# Power_main_DCDC.net
KiCad netlist of a schematic drawn in Altium Designer
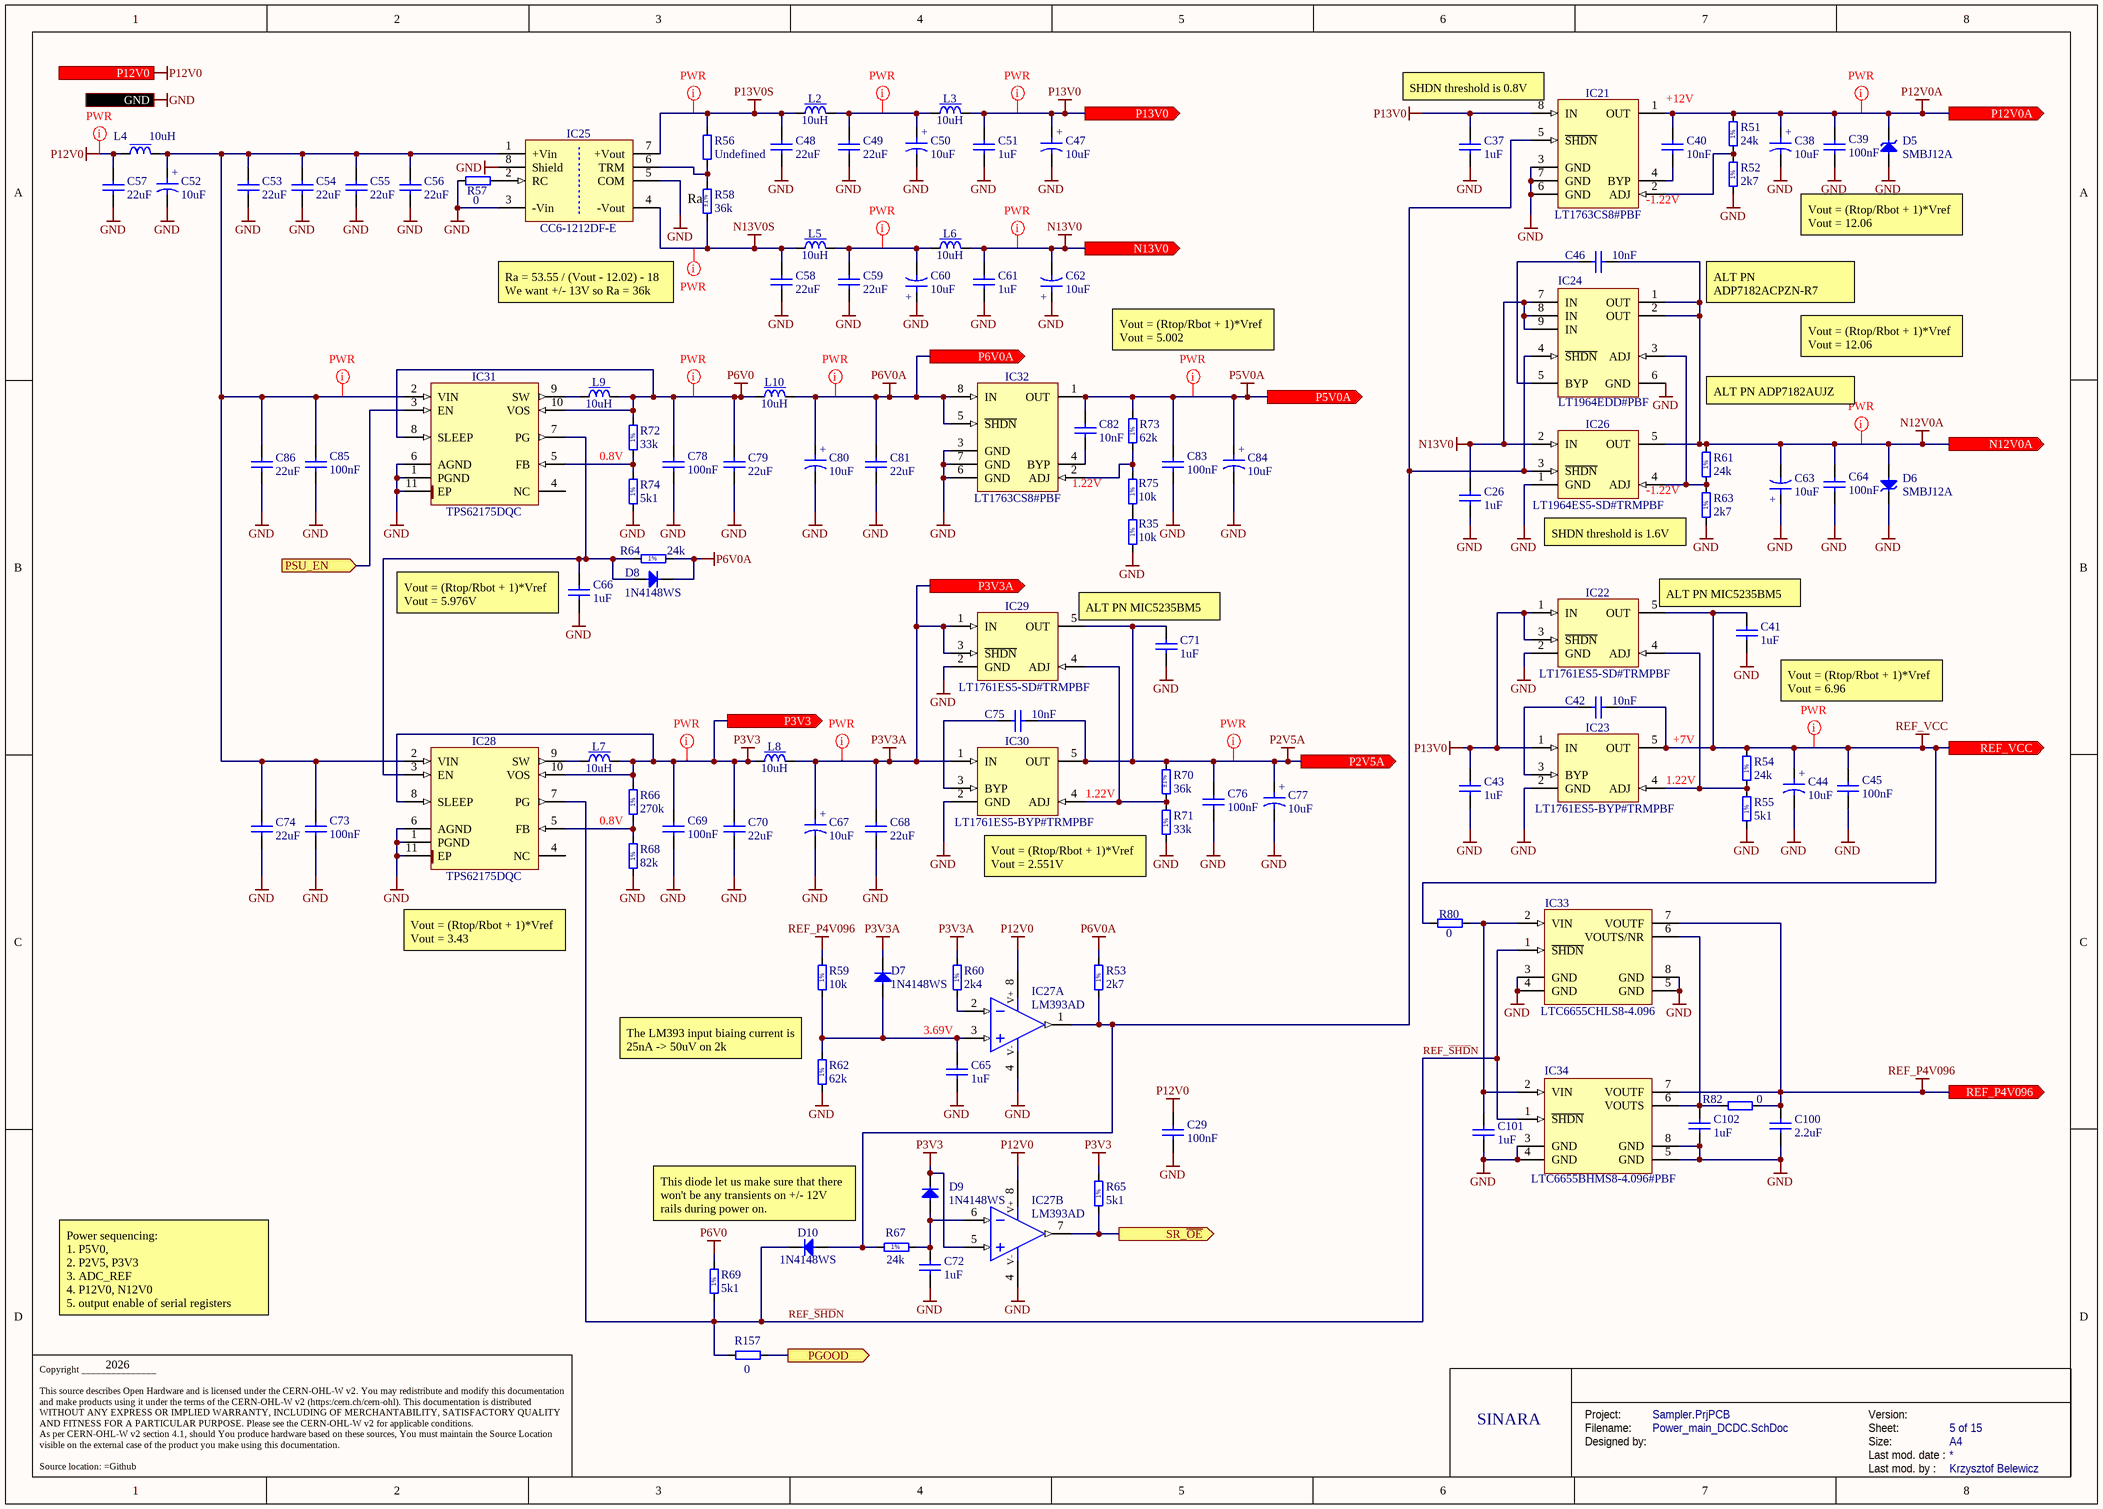
[diagram p0: Power_main_DCDC.SchDoc]

(export (version "E")
  (design (tool "Eeschema 10.0.6"))
  (components
    (comp (ref "C26")
      (value "1uF")
      (footprint "CAPC1608X87N")
      (description "Non-polarised capacitor")
      (fields
        (field (name "PART NUMBER") "CC0603_1UF_25V_10%_X7R")
        (field (name "VOLTAGE") "25V")
        (field (name "AUTHOR") "CERN DEM JLC")
      )
      (libsource (lib "Capacitors") (part "Capacitor - non polarized"))
    )
    (comp (ref "C29")
      (value "100nF")
      (footprint "CAPC1005X55N")
      (description "Non-polarised capacitor")
      (fields
        (field (name "PART NUMBER") "CC0402_100NF_50V_10%_X7R")
        (field (name "VOLTAGE") "50V")
        (field (name "AUTHOR") "CERN DEM MR")
      )
      (libsource (lib "Capacitors") (part "Capacitor - non polarized"))
    )
    (comp (ref "C37")
      (value "1uF")
      (footprint "CAPC1608X87N")
      (description "Non-polarised capacitor")
      (fields
        (field (name "PART NUMBER") "CC0603_1UF_25V_10%_X7R")
        (field (name "VOLTAGE") "25V")
        (field (name "AUTHOR") "CERN DEM JLC")
      )
      (libsource (lib "Capacitors") (part "Capacitor - non polarized"))
    )
    (comp (ref "C38")
      (value "10uF")
      (footprint "CAPMP3216X180N")
      (description "Polarised capacitor")
      (fields
        (field (name "PART NUMBER") "CTE3216-18_10UF_16V_20%_AVX_TCJ")
        (field (name "VOLTAGE") "16V")
        (field (name "AUTHOR") "CERN DEM JLC")
      )
      (libsource (lib "Capacitors") (part "Capacitor - polarized"))
    )
    (comp (ref "C39")
      (value "100nF")
      (footprint "CAPC1005X55N")
      (description "Non-polarised capacitor")
      (fields
        (field (name "PART NUMBER") "CC0402_100NF_50V_10%_X7R")
        (field (name "VOLTAGE") "50V")
        (field (name "AUTHOR") "CERN DEM MR")
      )
      (libsource (lib "Capacitors") (part "Capacitor - non polarized"))
    )
    (comp (ref "C40")
      (value "10nF")
      (footprint "CAPC1005X55N")
      (description "Non-polarised capacitor")
      (fields
        (field (name "PART NUMBER") "CC0402_10NF_50V_5%_X7R")
        (field (name "VOLTAGE") "50V")
        (field (name "AUTHOR") "CERN DEM BC")
      )
      (libsource (lib "Capacitors") (part "Capacitor - non polarized"))
    )
    (comp (ref "C41")
      (value "1uF")
      (footprint "CAPC1608X87N")
      (description "Non-polarised capacitor")
      (fields
        (field (name "PART NUMBER") "CC0603_1UF_25V_10%_X7R")
        (field (name "VOLTAGE") "25V")
        (field (name "AUTHOR") "CERN DEM JLC")
      )
      (libsource (lib "Capacitors") (part "Capacitor - non polarized"))
    )
    (comp (ref "C42")
      (value "10nF")
      (footprint "CAPC1005X55N")
      (description "Non-polarised capacitor")
      (fields
        (field (name "PART NUMBER") "CC0402_10NF_50V_5%_X7R")
        (field (name "VOLTAGE") "50V")
        (field (name "AUTHOR") "CERN DEM BC")
      )
      (libsource (lib "Capacitors") (part "Capacitor - non polarized"))
    )
    (comp (ref "C43")
      (value "1uF")
      (footprint "CAPC1608X87N")
      (description "Non-polarised capacitor")
      (fields
        (field (name "PART NUMBER") "CC0603_1UF_25V_10%_X7R")
        (field (name "VOLTAGE") "25V")
        (field (name "AUTHOR") "CERN DEM JLC")
      )
      (libsource (lib "Capacitors") (part "Capacitor - non polarized"))
    )
    (comp (ref "C44")
      (value "10uF")
      (footprint "CAPMP3216X180N")
      (description "Polarised capacitor")
      (fields
        (field (name "PART NUMBER") "CTE3216-18_10UF_16V_20%_AVX_TCJ")
        (field (name "VOLTAGE") "16V")
        (field (name "AUTHOR") "CERN DEM JLC")
      )
      (libsource (lib "Capacitors") (part "Capacitor - polarized"))
    )
    (comp (ref "C45")
      (value "100nF")
      (footprint "CAPC1005X55N")
      (description "Non-polarised capacitor")
      (fields
        (field (name "PART NUMBER") "CC0402_100NF_50V_10%_X7R")
        (field (name "VOLTAGE") "50V")
        (field (name "AUTHOR") "CERN DEM MR")
      )
      (libsource (lib "Capacitors") (part "Capacitor - non polarized"))
    )
    (comp (ref "C46")
      (value "10nF")
      (footprint "CAPC1005X55N")
      (description "Non-polarised capacitor")
      (fields
        (field (name "PART NUMBER") "CC0402_10NF_50V_5%_X7R")
        (field (name "VOLTAGE") "50V")
        (field (name "AUTHOR") "CERN DEM BC")
      )
      (libsource (lib "Capacitors") (part "Capacitor - non polarized"))
    )
    (comp (ref "C47")
      (value "10uF")
      (footprint "CAPMP3216X180N")
      (description "Polarised capacitor")
      (fields
        (field (name "PART NUMBER") "CTE3216-18_10UF_16V_20%_AVX_TCJ")
        (field (name "VOLTAGE") "16V")
        (field (name "AUTHOR") "CERN DEM JLC")
      )
      (libsource (lib "Capacitors") (part "Capacitor - polarized"))
    )
    (comp (ref "C48")
      (value "22uF")
      (footprint "CAPC2012X135N")
      (description "Non-polarised capacitor")
      (fields
        (field (name "PART NUMBER") "CC0805_22UF_16V_10%_X5R")
        (field (name "VOLTAGE") "16V")
        (field (name "AUTHOR") "CERN DEM JLC")
      )
      (libsource (lib "Capacitors") (part "Capacitor - non polarized"))
    )
    (comp (ref "C49")
      (value "22uF")
      (footprint "CAPC2012X135N")
      (description "Non-polarised capacitor")
      (fields
        (field (name "PART NUMBER") "CC0805_22UF_16V_10%_X5R")
        (field (name "VOLTAGE") "16V")
        (field (name "AUTHOR") "CERN DEM JLC")
      )
      (libsource (lib "Capacitors") (part "Capacitor - non polarized"))
    )
    (comp (ref "C50")
      (value "10uF")
      (footprint "CAPMP3216X180N")
      (description "Polarised capacitor")
      (fields
        (field (name "PART NUMBER") "CTE3216-18_10UF_16V_20%_AVX_TCJ")
        (field (name "VOLTAGE") "16V")
        (field (name "AUTHOR") "CERN DEM JLC")
      )
      (libsource (lib "Capacitors") (part "Capacitor - polarized"))
    )
    (comp (ref "C51")
      (value "1uF")
      (footprint "CAPC1608X87N")
      (description "Non-polarised capacitor")
      (fields
        (field (name "PART NUMBER") "CC0603_1UF_25V_10%_X7R")
        (field (name "VOLTAGE") "25V")
        (field (name "AUTHOR") "CERN DEM JLC")
      )
      (libsource (lib "Capacitors") (part "Capacitor - non polarized"))
    )
    (comp (ref "C52")
      (value "10uF")
      (footprint "CAPMP3216X180N")
      (description "Polarised capacitor")
      (fields
        (field (name "PART NUMBER") "CTE3216-18_10UF_16V_20%_AVX_TCJ")
        (field (name "VOLTAGE") "16V")
        (field (name "AUTHOR") "CERN DEM JLC")
      )
      (libsource (lib "Capacitors") (part "Capacitor - polarized"))
    )
    (comp (ref "C53")
      (value "22uF")
      (footprint "CAPC2012X135N")
      (description "Non-polarised capacitor")
      (fields
        (field (name "PART NUMBER") "CC0805_22UF_16V_10%_X5R")
        (field (name "VOLTAGE") "16V")
        (field (name "AUTHOR") "CERN DEM JLC")
      )
      (libsource (lib "Capacitors") (part "Capacitor - non polarized"))
    )
    (comp (ref "C54")
      (value "22uF")
      (footprint "CAPC2012X135N")
      (description "Non-polarised capacitor")
      (fields
        (field (name "PART NUMBER") "CC0805_22UF_16V_10%_X5R")
        (field (name "VOLTAGE") "16V")
        (field (name "AUTHOR") "CERN DEM JLC")
      )
      (libsource (lib "Capacitors") (part "Capacitor - non polarized"))
    )
    (comp (ref "C55")
      (value "22uF")
      (footprint "CAPC2012X135N")
      (description "Non-polarised capacitor")
      (fields
        (field (name "PART NUMBER") "CC0805_22UF_16V_10%_X5R")
        (field (name "VOLTAGE") "16V")
        (field (name "AUTHOR") "CERN DEM JLC")
      )
      (libsource (lib "Capacitors") (part "Capacitor - non polarized"))
    )
    (comp (ref "C56")
      (value "22uF")
      (footprint "CAPC2012X135N")
      (description "Non-polarised capacitor")
      (fields
        (field (name "PART NUMBER") "CC0805_22UF_16V_10%_X5R")
        (field (name "VOLTAGE") "16V")
        (field (name "AUTHOR") "CERN DEM JLC")
      )
      (libsource (lib "Capacitors") (part "Capacitor - non polarized"))
    )
    (comp (ref "C57")
      (value "22uF")
      (footprint "CAPC2012X135N")
      (description "Non-polarised capacitor")
      (fields
        (field (name "PART NUMBER") "CC0805_22UF_16V_10%_X5R")
        (field (name "VOLTAGE") "16V")
        (field (name "AUTHOR") "CERN DEM JLC")
      )
      (libsource (lib "Capacitors") (part "Capacitor - non polarized"))
    )
    (comp (ref "C58")
      (value "22uF")
      (footprint "CAPC2012X135N")
      (description "Non-polarised capacitor")
      (fields
        (field (name "PART NUMBER") "CC0805_22UF_16V_10%_X5R")
        (field (name "VOLTAGE") "16V")
        (field (name "AUTHOR") "CERN DEM JLC")
      )
      (libsource (lib "Capacitors") (part "Capacitor - non polarized"))
    )
    (comp (ref "C59")
      (value "22uF")
      (footprint "CAPC2012X135N")
      (description "Non-polarised capacitor")
      (fields
        (field (name "PART NUMBER") "CC0805_22UF_16V_10%_X5R")
        (field (name "VOLTAGE") "16V")
        (field (name "AUTHOR") "CERN DEM JLC")
      )
      (libsource (lib "Capacitors") (part "Capacitor - non polarized"))
    )
    (comp (ref "C60")
      (value "10uF")
      (footprint "CAPMP3216X180N")
      (description "Polarised capacitor")
      (fields
        (field (name "PART NUMBER") "CTE3216-18_10UF_16V_20%_AVX_TCJ")
        (field (name "VOLTAGE") "16V")
        (field (name "AUTHOR") "CERN DEM JLC")
      )
      (libsource (lib "Capacitors") (part "Capacitor - polarized"))
    )
    (comp (ref "C61")
      (value "1uF")
      (footprint "CAPC1608X87N")
      (description "Non-polarised capacitor")
      (fields
        (field (name "PART NUMBER") "CC0603_1UF_25V_10%_X7R")
        (field (name "VOLTAGE") "25V")
        (field (name "AUTHOR") "CERN DEM JLC")
      )
      (libsource (lib "Capacitors") (part "Capacitor - non polarized"))
    )
    (comp (ref "C62")
      (value "10uF")
      (footprint "CAPMP3216X180N")
      (description "Polarised capacitor")
      (fields
        (field (name "PART NUMBER") "CTE3216-18_10UF_16V_20%_AVX_TCJ")
        (field (name "VOLTAGE") "16V")
        (field (name "AUTHOR") "CERN DEM JLC")
      )
      (libsource (lib "Capacitors") (part "Capacitor - polarized"))
    )
    (comp (ref "C63")
      (value "10uF")
      (footprint "CAPMP3216X180N")
      (description "Polarised capacitor")
      (fields
        (field (name "PART NUMBER") "CTE3216-18_10UF_16V_20%_AVX_TCJ")
        (field (name "VOLTAGE") "16V")
        (field (name "AUTHOR") "CERN DEM JLC")
      )
      (libsource (lib "Capacitors") (part "Capacitor - polarized"))
    )
    (comp (ref "C64")
      (value "100nF")
      (footprint "CAPC1005X55N")
      (description "Non-polarised capacitor")
      (fields
        (field (name "PART NUMBER") "CC0402_100NF_50V_10%_X7R")
        (field (name "VOLTAGE") "50V")
        (field (name "AUTHOR") "CERN DEM MR")
      )
      (libsource (lib "Capacitors") (part "Capacitor - non polarized"))
    )
    (comp (ref "C65")
      (value "1uF")
      (footprint "CAPC1608X87N")
      (description "Non-polarised capacitor")
      (fields
        (field (name "PART NUMBER") "CC0603_1UF_25V_10%_X7R")
        (field (name "VOLTAGE") "25V")
        (field (name "AUTHOR") "CERN DEM JLC")
      )
      (libsource (lib "Capacitors") (part "Capacitor - non polarized"))
    )
    (comp (ref "C66")
      (value "1uF")
      (footprint "CAPC1608X87N")
      (description "Non-polarised capacitor")
      (fields
        (field (name "PART NUMBER") "CC0603_1UF_25V_10%_X7R")
        (field (name "VOLTAGE") "25V")
        (field (name "AUTHOR") "CERN DEM JLC")
      )
      (libsource (lib "Capacitors") (part "Capacitor - non polarized"))
    )
    (comp (ref "C67")
      (value "10uF")
      (footprint "CAPMP3216X180N")
      (description "Polarised capacitor")
      (fields
        (field (name "PART NUMBER") "CTE3216-18_10UF_16V_20%_AVX_TCJ")
        (field (name "VOLTAGE") "16V")
        (field (name "AUTHOR") "CERN DEM JLC")
      )
      (libsource (lib "Capacitors") (part "Capacitor - polarized"))
    )
    (comp (ref "C68")
      (value "22uF")
      (footprint "CAPC2012X135N")
      (description "Non-polarised capacitor")
      (fields
        (field (name "PART NUMBER") "CC0805_22UF_16V_10%_X5R")
        (field (name "VOLTAGE") "16V")
        (field (name "AUTHOR") "CERN DEM JLC")
      )
      (libsource (lib "Capacitors") (part "Capacitor - non polarized"))
    )
    (comp (ref "C69")
      (value "100nF")
      (footprint "CAPC1005X55N")
      (description "Non-polarised capacitor")
      (fields
        (field (name "PART NUMBER") "CC0402_100NF_50V_10%_X7R")
        (field (name "VOLTAGE") "50V")
        (field (name "AUTHOR") "CERN DEM MR")
      )
      (libsource (lib "Capacitors") (part "Capacitor - non polarized"))
    )
    (comp (ref "C70")
      (value "22uF")
      (footprint "CAPC2012X135N")
      (description "Non-polarised capacitor")
      (fields
        (field (name "PART NUMBER") "CC0805_22UF_16V_10%_X5R")
        (field (name "VOLTAGE") "16V")
        (field (name "AUTHOR") "CERN DEM JLC")
      )
      (libsource (lib "Capacitors") (part "Capacitor - non polarized"))
    )
    (comp (ref "C71")
      (value "1uF")
      (footprint "CAPC1608X87N")
      (description "Non-polarised capacitor")
      (fields
        (field (name "PART NUMBER") "CC0603_1UF_25V_10%_X7R")
        (field (name "VOLTAGE") "25V")
        (field (name "AUTHOR") "CERN DEM JLC")
      )
      (libsource (lib "Capacitors") (part "Capacitor - non polarized"))
    )
    (comp (ref "C72")
      (value "1uF")
      (footprint "CAPC1608X87N")
      (description "Non-polarised capacitor")
      (fields
        (field (name "PART NUMBER") "CC0603_1UF_25V_10%_X7R")
        (field (name "VOLTAGE") "25V")
        (field (name "AUTHOR") "CERN DEM JLC")
      )
      (libsource (lib "Capacitors") (part "Capacitor - non polarized"))
    )
    (comp (ref "C73")
      (value "100nF")
      (footprint "CAPC1005X55N")
      (description "Non-polarised capacitor")
      (fields
        (field (name "PART NUMBER") "CC0402_100NF_50V_10%_X7R")
        (field (name "VOLTAGE") "50V")
        (field (name "AUTHOR") "CERN DEM MR")
      )
      (libsource (lib "Capacitors") (part "Capacitor - non polarized"))
    )
    (comp (ref "C74")
      (value "22uF")
      (footprint "CAPC2012X135N")
      (description "Non-polarised capacitor")
      (fields
        (field (name "PART NUMBER") "CC0805_22UF_16V_10%_X5R")
        (field (name "VOLTAGE") "16V")
        (field (name "AUTHOR") "CERN DEM JLC")
      )
      (libsource (lib "Capacitors") (part "Capacitor - non polarized"))
    )
    (comp (ref "C75")
      (value "10nF")
      (footprint "CAPC1005X55N")
      (description "Non-polarised capacitor")
      (fields
        (field (name "PART NUMBER") "CC0402_10NF_50V_5%_X7R")
        (field (name "VOLTAGE") "50V")
        (field (name "AUTHOR") "CERN DEM BC")
      )
      (libsource (lib "Capacitors") (part "Capacitor - non polarized"))
    )
    (comp (ref "C76")
      (value "100nF")
      (footprint "CAPC1005X55N")
      (description "Non-polarised capacitor")
      (fields
        (field (name "PART NUMBER") "CC0402_100NF_50V_10%_X7R")
        (field (name "VOLTAGE") "50V")
        (field (name "AUTHOR") "CERN DEM MR")
      )
      (libsource (lib "Capacitors") (part "Capacitor - non polarized"))
    )
    (comp (ref "C77")
      (value "10uF")
      (footprint "CAPMP3216X180N")
      (description "Polarised capacitor")
      (fields
        (field (name "PART NUMBER") "CTE3216-18_10UF_16V_20%_AVX_TCJ")
        (field (name "VOLTAGE") "16V")
        (field (name "AUTHOR") "CERN DEM JLC")
      )
      (libsource (lib "Capacitors") (part "Capacitor - polarized"))
    )
    (comp (ref "C78")
      (value "100nF")
      (footprint "CAPC1005X55N")
      (description "Non-polarised capacitor")
      (fields
        (field (name "PART NUMBER") "CC0402_100NF_50V_10%_X7R")
        (field (name "VOLTAGE") "50V")
        (field (name "AUTHOR") "CERN DEM MR")
      )
      (libsource (lib "Capacitors") (part "Capacitor - non polarized"))
    )
    (comp (ref "C79")
      (value "22uF")
      (footprint "CAPC2012X135N")
      (description "Non-polarised capacitor")
      (fields
        (field (name "PART NUMBER") "CC0805_22UF_16V_10%_X5R")
        (field (name "VOLTAGE") "16V")
        (field (name "AUTHOR") "CERN DEM JLC")
      )
      (libsource (lib "Capacitors") (part "Capacitor - non polarized"))
    )
    (comp (ref "C80")
      (value "10uF")
      (footprint "CAPMP3216X180N")
      (description "Polarised capacitor")
      (fields
        (field (name "PART NUMBER") "CTE3216-18_10UF_16V_20%_AVX_TCJ")
        (field (name "VOLTAGE") "16V")
        (field (name "AUTHOR") "CERN DEM JLC")
      )
      (libsource (lib "Capacitors") (part "Capacitor - polarized"))
    )
    (comp (ref "C81")
      (value "22uF")
      (footprint "CAPC2012X135N")
      (description "Non-polarised capacitor")
      (fields
        (field (name "PART NUMBER") "CC0805_22UF_16V_10%_X5R")
        (field (name "VOLTAGE") "16V")
        (field (name "AUTHOR") "CERN DEM JLC")
      )
      (libsource (lib "Capacitors") (part "Capacitor - non polarized"))
    )
    (comp (ref "C82")
      (value "10nF")
      (footprint "CAPC1005X55N")
      (description "Non-polarised capacitor")
      (fields
        (field (name "PART NUMBER") "CC0402_10NF_50V_5%_X7R")
        (field (name "VOLTAGE") "50V")
        (field (name "AUTHOR") "CERN DEM BC")
      )
      (libsource (lib "Capacitors") (part "Capacitor - non polarized"))
    )
    (comp (ref "C83")
      (value "100nF")
      (footprint "CAPC1005X55N")
      (description "Non-polarised capacitor")
      (fields
        (field (name "PART NUMBER") "CC0402_100NF_50V_10%_X7R")
        (field (name "VOLTAGE") "50V")
        (field (name "AUTHOR") "CERN DEM MR")
      )
      (libsource (lib "Capacitors") (part "Capacitor - non polarized"))
    )
    (comp (ref "C84")
      (value "10uF")
      (footprint "CAPMP3216X180N")
      (description "Polarised capacitor")
      (fields
        (field (name "PART NUMBER") "CTE3216-18_10UF_16V_20%_AVX_TCJ")
        (field (name "VOLTAGE") "16V")
        (field (name "AUTHOR") "CERN DEM JLC")
      )
      (libsource (lib "Capacitors") (part "Capacitor - polarized"))
    )
    (comp (ref "C85")
      (value "100nF")
      (footprint "CAPC1005X55N")
      (description "Non-polarised capacitor")
      (fields
        (field (name "PART NUMBER") "CC0402_100NF_50V_10%_X7R")
        (field (name "VOLTAGE") "50V")
        (field (name "AUTHOR") "CERN DEM MR")
      )
      (libsource (lib "Capacitors") (part "Capacitor - non polarized"))
    )
    (comp (ref "C86")
      (value "22uF")
      (footprint "CAPC2012X135N")
      (description "Non-polarised capacitor")
      (fields
        (field (name "PART NUMBER") "CC0805_22UF_16V_10%_X5R")
        (field (name "VOLTAGE") "16V")
        (field (name "AUTHOR") "CERN DEM JLC")
      )
      (libsource (lib "Capacitors") (part "Capacitor - non polarized"))
    )
    (comp (ref "C100")
      (value "2.2uF")
      (footprint "CAPC1608X87N")
      (description "Non-polarised capacitor")
      (fields
        (field (name "PART NUMBER") "CC0603_2.2UF_16V_10%_X5R")
        (field (name "VOLTAGE") "16V")
        (field (name "AUTHOR") "CERN DEM JLC")
      )
      (libsource (lib "Capacitors") (part "Capacitor - non polarized"))
    )
    (comp (ref "C101")
      (value "1uF")
      (footprint "CAPC1608X87N")
      (description "Non-polarised capacitor")
      (fields
        (field (name "PART NUMBER") "CC0603_1UF_25V_10%_X7R")
        (field (name "VOLTAGE") "25V")
        (field (name "AUTHOR") "CERN DEM JLC")
      )
      (libsource (lib "Capacitors") (part "Capacitor - non polarized"))
    )
    (comp (ref "C102")
      (value "1uF")
      (footprint "CAPC1608X87N")
      (description "Non-polarised capacitor")
      (fields
        (field (name "PART NUMBER") "CC0603_1UF_25V_10%_X7R")
        (field (name "VOLTAGE") "25V")
        (field (name "AUTHOR") "CERN DEM JLC")
      )
      (libsource (lib "Capacitors") (part "Capacitor - non polarized"))
    )
    (comp (ref "D5")
      (value "SMBJ12A")
      (footprint "DIOM5336X265N")
      (description "Zener Diode")
      (fields
        (field (name "VOLTAGE") "12V")
        (field (name "POWER") "600W")
        (field (name "AUTHOR") "CERN DEM JLC")
      )
      (libsource (lib "ICs And Semiconductors") (part "Diode Zener"))
    )
    (comp (ref "D6")
      (value "SMBJ12A")
      (footprint "DIOM5336X265N")
      (description "Zener Diode")
      (fields
        (field (name "VOLTAGE") "12V")
        (field (name "POWER") "600W")
        (field (name "AUTHOR") "CERN DEM JLC")
      )
      (libsource (lib "ICs And Semiconductors") (part "Diode Zener"))
    )
    (comp (ref "D7")
      (value "1N4148WS")
      (footprint "SODFL2512X100N")
      (description "Diode")
      (fields
        (field (name "VOLTAGE") "75V")
        (field (name "POWER") "150mA")
        (field (name "AUTHOR") "CERN DEM JLC")
      )
      (libsource (lib "ICs And Semiconductors") (part "Diode"))
    )
    (comp (ref "D8")
      (value "1N4148WS")
      (footprint "SODFL2512X100N")
      (description "Diode")
      (fields
        (field (name "VOLTAGE") "75V")
        (field (name "POWER") "150mA")
        (field (name "AUTHOR") "CERN DEM JLC")
      )
      (libsource (lib "ICs And Semiconductors") (part "Diode"))
    )
    (comp (ref "D9")
      (value "1N4148WS")
      (footprint "SODFL2512X100N")
      (description "Diode")
      (fields
        (field (name "VOLTAGE") "75V")
        (field (name "POWER") "150mA")
        (field (name "AUTHOR") "CERN DEM JLC")
      )
      (libsource (lib "ICs And Semiconductors") (part "Diode"))
    )
    (comp (ref "D10")
      (value "1N4148WS")
      (footprint "SODFL2512X100N")
      (description "Diode")
      (fields
        (field (name "VOLTAGE") "75V")
        (field (name "POWER") "150mA")
        (field (name "AUTHOR") "CERN DEM JLC")
      )
      (libsource (lib "ICs And Semiconductors") (part "Diode"))
    )
    (comp (ref "IC21")
      (value "LT1763CS8#PBF")
      (footprint "SOIC127P600X175-8N")
      (description "1.22V to 20V 500mA, Low Noise, LDO Adjustable Micropower Regulator")
      (fields (field (name "MANUFACTURER") "LINEAR TECHNOLOGY") (field (name "AUTHOR") "CERN DEM JLC"))
      (libsource (lib "ICs And Semiconductors") (part "LT1763xS8"))
    )
    (comp (ref "IC22")
      (value "LT1761ES5-SD#TRMPBF")
      (footprint "SOT95P280X100-5N")
      (description "100mA, Low Noise, LDO Micropower Adjustable Regulator in SOT-23")
      (fields (field (name "MANUFACTURER") "LINEAR TECHNOLOGY") (field (name "AUTHOR") "CERN DEM JLC"))
      (libsource (lib "ICs And Semiconductors") (part "LT1761-SD"))
    )
    (comp (ref "IC23")
      (value "LT1761ES5-BYP#TRMPBF")
      (footprint "SOT95P280X100-5N")
      (description "100mA, Low Noise, LDO Micropower Adjustable Regulator in SOT-23")
      (fields (field (name "MANUFACTURER") "LINEAR TECHNOLOGY") (field (name "AUTHOR") "CERN DEM MR"))
      (libsource (lib "ICs And Semiconductors") (part "LT1761-BYP"))
    )
    (comp (ref "IC24")
      (value "LT1964EDD#PBF")
      (footprint "LT-DD-8_V")
      (fields (field (name "MANUFACTURER") "Linear Technology"))
      (libsource (lib "Altium Content Vault") (part "LT-LT1964-DD-8"))
    )
    (comp (ref "IC25")
      (value "CC6-1212DF-E")
      (footprint "CC6-1212DF-E")
      (description "CONV DC/DC 6W DUAL 12V +-12V PCB")
      (fields (field (name "MANUFACTURER") "TDK-Lambda Americas Inc.") (field (name "AUTHOR") "GK"))
      (libsource (lib "Regulators_SMPS") (part "DC/DC_CC6-1212DF-E"))
    )
    (comp (ref "IC26")
      (value "LT1964ES5-SD#TRMPBF")
      (footprint "SOT95P280X100-5N")
      (description "200mA, Low Noise, Low Dropout Negative Micropower Regulator")
      (fields (field (name "MANUFACTURER") "LINEAR TECHNOLOGY") (field (name "AUTHOR") "CERN DEM JLC"))
      (libsource (lib "ICs And Semiconductors") (part "LT1964-SD"))
    )
    (comp (ref "IC27")
      (value "LM393AD")
      (footprint "SOIC127P600X175-8N")
      (description "Dual Operational Amplifier")
      (fields (field (name "MANUFACTURER") "TEXAS INSTRUMENTS") (field (name "AUTHOR") "CERN DEM JLC"))
      (libsource (lib "ICs And Semiconductors") (part "Operational Amplifier x2 Type1"))
    )
    (comp (ref "IC28")
      (value "TPS62175DQC")
      (footprint "SON50P200X300X80-11N-R94X250")
      (description "4.75-28VDC to 1-6VDC, 500mA Step-Down Converter With Sleep Mode")
      (fields (field (name "MANUFACTURER") "TEXAS INSTRUMENTS") (field (name "AUTHOR") "CERN DEM JMW"))
      (libsource (lib "ICs And Semiconductors") (part "TPS62175"))
    )
    (comp (ref "IC29")
      (value "LT1761ES5-SD#TRMPBF")
      (footprint "SOT95P280X100-5N")
      (description "100mA, Low Noise, LDO Micropower Adjustable Regulator in SOT-23")
      (fields (field (name "MANUFACTURER") "LINEAR TECHNOLOGY") (field (name "AUTHOR") "CERN DEM JLC"))
      (libsource (lib "ICs And Semiconductors") (part "LT1761-SD"))
    )
    (comp (ref "IC30")
      (value "LT1761ES5-BYP#TRMPBF")
      (footprint "SOT95P280X100-5N")
      (description "100mA, Low Noise, LDO Micropower Adjustable Regulator in SOT-23")
      (fields (field (name "MANUFACTURER") "LINEAR TECHNOLOGY") (field (name "AUTHOR") "CERN DEM MR"))
      (libsource (lib "ICs And Semiconductors") (part "LT1761-BYP"))
    )
    (comp (ref "IC31")
      (value "TPS62175DQC")
      (footprint "SON50P200X300X80-11N-R94X250")
      (description "4.75-28VDC to 1-6VDC, 500mA Step-Down Converter With Sleep Mode")
      (fields (field (name "MANUFACTURER") "TEXAS INSTRUMENTS") (field (name "AUTHOR") "CERN DEM JMW"))
      (libsource (lib "ICs And Semiconductors") (part "TPS62175"))
    )
    (comp (ref "IC32")
      (value "LT1763CS8#PBF")
      (footprint "SOIC127P600X175-8N")
      (description "1.22V to 20V 500mA, Low Noise, LDO Adjustable Micropower Regulator")
      (fields (field (name "MANUFACTURER") "LINEAR TECHNOLOGY") (field (name "AUTHOR") "CERN DEM JLC"))
      (libsource (lib "ICs And Semiconductors") (part "LT1763xS8"))
    )
    (comp (ref "IC33")
      (value "LTC6655CHLS8-4.096")
      (footprint "LCCS127P500X500X145-8N")
      (description "4.096, 1uA Precision Voltage Reference")
      (fields
        (field (name "PART NUMBER") "LTC6655CHLS8-4.096#PBF")
        (field (name "MANUFACTURER") "LINEAR TECHNOLOGY")
        (field (name "AUTHOR") "GK")
      )
      (libsource (lib "ICs_Analog_Interfaces") (part "REF_LTC6655CHLS8-4.096"))
    )
    (comp (ref "IC34")
      (value "LTC6655BHMS8-4.096#PBF")
      (footprint "SOP65P490X110-8N")
      (description "0.25ppm Noise, Low Drift Precision Buffered Voltage Reference")
      (fields (field (name "MANUFACTURER") "LINEAR TECHNOLOGY") (field (name "AUTHOR") "GK"))
      (libsource (lib "LIBRARY_SCH") (part "REF_LTC6655"))
    )
    (comp (ref "L2")
      (value "10uH")
      (footprint "IND_MURATA-PS_8400")
      (description "Inductor With Core")
      (fields
        (field (name "PART NUMBER") "IND_10UH_10%_MURATA-PS_8400")
        (field (name "POWER") "950mA")
        (field (name "AUTHOR") "CERN DEM JLC")
      )
      (libsource (lib "Inductors & Transformers") (part "Inductor With Magnetic core"))
    )
    (comp (ref "L3")
      (value "10uH")
      (footprint "IND_MURATA-PS_8400")
      (description "Inductor With Core")
      (fields
        (field (name "PART NUMBER") "IND_10UH_10%_MURATA-PS_8400")
        (field (name "POWER") "950mA")
        (field (name "AUTHOR") "CERN DEM JLC")
      )
      (libsource (lib "Inductors & Transformers") (part "Inductor With Magnetic core"))
    )
    (comp (ref "L4")
      (value "10uH")
      (footprint "IND_MURATA-PS_8400")
      (description "Inductor With Core")
      (fields
        (field (name "PART NUMBER") "IND_10UH_10%_MURATA-PS_8400")
        (field (name "POWER") "950mA")
        (field (name "AUTHOR") "CERN DEM JLC")
      )
      (libsource (lib "Inductors & Transformers") (part "Inductor With Magnetic core"))
    )
    (comp (ref "L5")
      (value "10uH")
      (footprint "IND_MURATA-PS_8400")
      (description "Inductor With Core")
      (fields
        (field (name "PART NUMBER") "IND_10UH_10%_MURATA-PS_8400")
        (field (name "POWER") "950mA")
        (field (name "AUTHOR") "CERN DEM JLC")
      )
      (libsource (lib "Inductors & Transformers") (part "Inductor With Magnetic core"))
    )
    (comp (ref "L6")
      (value "10uH")
      (footprint "IND_MURATA-PS_8400")
      (description "Inductor With Core")
      (fields
        (field (name "PART NUMBER") "IND_10UH_10%_MURATA-PS_8400")
        (field (name "POWER") "950mA")
        (field (name "AUTHOR") "CERN DEM JLC")
      )
      (libsource (lib "Inductors & Transformers") (part "Inductor With Magnetic core"))
    )
    (comp (ref "L7")
      (value "10uH")
      (footprint "IND_MURATA-PS_8400")
      (description "Inductor With Core")
      (fields
        (field (name "PART NUMBER") "IND_10UH_10%_MURATA-PS_8400")
        (field (name "POWER") "950mA")
        (field (name "AUTHOR") "CERN DEM JLC")
      )
      (libsource (lib "Inductors & Transformers") (part "Inductor With Magnetic core"))
    )
    (comp (ref "L8")
      (value "10uH")
      (footprint "IND_MURATA-PS_8400")
      (description "Inductor With Core")
      (fields
        (field (name "PART NUMBER") "IND_10UH_10%_MURATA-PS_8400")
        (field (name "POWER") "950mA")
        (field (name "AUTHOR") "CERN DEM JLC")
      )
      (libsource (lib "Inductors & Transformers") (part "Inductor With Magnetic core"))
    )
    (comp (ref "L9")
      (value "10uH")
      (footprint "IND_MURATA-PS_8400")
      (description "Inductor With Core")
      (fields
        (field (name "PART NUMBER") "IND_10UH_10%_MURATA-PS_8400")
        (field (name "POWER") "950mA")
        (field (name "AUTHOR") "CERN DEM JLC")
      )
      (libsource (lib "Inductors & Transformers") (part "Inductor With Magnetic core"))
    )
    (comp (ref "L10")
      (value "10uH")
      (footprint "IND_MURATA-PS_8400")
      (description "Inductor With Core")
      (fields
        (field (name "PART NUMBER") "IND_10UH_10%_MURATA-PS_8400")
        (field (name "POWER") "950mA")
        (field (name "AUTHOR") "CERN DEM JLC")
      )
      (libsource (lib "Inductors & Transformers") (part "Inductor With Magnetic core"))
    )
    (comp (ref "R35")
      (value "10k")
      (footprint "RESC1005X40N")
      (description "Resistor - 1%")
      (fields
        (field (name "PART NUMBER") "R0402_10K_1%_0.0625W_100PPM")
        (field (name "POWER") "0.0625W")
        (field (name "AUTHOR") "CERN DEM JLC")
      )
      (libsource (lib "Resistors") (part "Resistor - 1%"))
    )
    (comp (ref "R51")
      (value "24k")
      (footprint "RESC1608X55N")
      (description "Resistor - 1%")
      (fields
        (field (name "PART NUMBER") "R0603_24K_1%_0.1W_100PPM")
        (field (name "POWER") "0.1W")
        (field (name "AUTHOR") "CERN DEM JLC")
      )
      (libsource (lib "Resistors") (part "Resistor - 1%"))
    )
    (comp (ref "R52")
      (value "2k7")
      (footprint "RESC1608X55N")
      (description "Resistor - 1%")
      (fields
        (field (name "PART NUMBER") "R0603_2K7_1%_0.1W_100PPM")
        (field (name "POWER") "0.1W")
        (field (name "AUTHOR") "CERN DEM JLC")
      )
      (libsource (lib "Resistors") (part "Resistor - 1%"))
    )
    (comp (ref "R53")
      (value "2k7")
      (footprint "RESC1608X55N")
      (description "Resistor - 1%")
      (fields
        (field (name "PART NUMBER") "R0603_2K7_1%_0.1W_100PPM")
        (field (name "POWER") "0.1W")
        (field (name "AUTHOR") "CERN DEM JLC")
      )
      (libsource (lib "Resistors") (part "Resistor - 1%"))
    )
    (comp (ref "R54")
      (value "24k")
      (footprint "RESC1608X55N")
      (description "Resistor - 1%")
      (fields
        (field (name "PART NUMBER") "R0603_24K_1%_0.1W_100PPM")
        (field (name "POWER") "0.1W")
        (field (name "AUTHOR") "CERN DEM JLC")
      )
      (libsource (lib "Resistors") (part "Resistor - 1%"))
    )
    (comp (ref "R55")
      (value "5k1")
      (footprint "RESC1005X40N")
      (description "Resistor - 1%")
      (fields
        (field (name "PART NUMBER") "R0402_5K1_1%_0.0625W_100PPM")
        (field (name "POWER") "0.0625W")
        (field (name "AUTHOR") "CERN DEM JLC")
      )
      (libsource (lib "Resistors") (part "Resistor - 1%"))
    )
    (comp (ref "R56")
      (value "Undefined")
      (footprint "RESC1608X55N")
      (description "Resistor")
      (fields (field (name "PART NUMBER") "R0603_NO-VALUE") (field (name "AUTHOR") "CERN DEM JLC"))
      (libsource (lib "Resistors") (part "Resistor"))
    )
    (comp (ref "R57")
      (value "0")
      (footprint "RESC1005X40N")
      (description "Resistor")
      (fields
        (field (name "PART NUMBER") "R0402_0R_JUMPER")
        (field (name "MANUFACTURER") "GENERIC")
        (field (name "AUTHOR") "CERN DEM JLC")
      )
      (libsource (lib "Resistors") (part "Resistor"))
    )
    (comp (ref "R58")
      (value "36k")
      (footprint "RESC1608X55N")
      (description "Resistor - 1%")
      (fields
        (field (name "PART NUMBER") "R0603_36K_1%_0.1W_100PPM")
        (field (name "POWER") "0.1W")
        (field (name "TOLERANCE") "±1%")
        (field (name "AUTHOR") "CERN DEM JLC")
      )
      (libsource (lib "") (part "Resistor - 1%_1"))
    )
    (comp (ref "R59")
      (value "10k")
      (footprint "RESC1005X40N")
      (description "Resistor - 1%")
      (fields
        (field (name "PART NUMBER") "R0402_10K_1%_0.0625W_100PPM")
        (field (name "POWER") "0.0625W")
        (field (name "AUTHOR") "CERN DEM JLC")
      )
      (libsource (lib "Resistors") (part "Resistor - 1%"))
    )
    (comp (ref "R60")
      (value "2k4")
      (footprint "RESC1005X40N")
      (description "Resistor - 1%")
      (fields
        (field (name "PART NUMBER") "R0402_2K4_1%_0.0625W_100PPM")
        (field (name "POWER") "0.0625W")
        (field (name "AUTHOR") "CERN DEM JLC")
      )
      (libsource (lib "Resistors") (part "Resistor - 1%"))
    )
    (comp (ref "R61")
      (value "24k")
      (footprint "RESC1608X55N")
      (description "Resistor - 1%")
      (fields
        (field (name "PART NUMBER") "R0603_24K_1%_0.1W_100PPM")
        (field (name "POWER") "0.1W")
        (field (name "AUTHOR") "CERN DEM JLC")
      )
      (libsource (lib "Resistors") (part "Resistor - 1%"))
    )
    (comp (ref "R62")
      (value "62k")
      (footprint "RESC1005X40N")
      (description "Resistor - 1%")
      (fields
        (field (name "PART NUMBER") "R0402_62K_1%_0.0625W_100PPM")
        (field (name "POWER") "0.0625W")
        (field (name "AUTHOR") "CERN DEM JLC")
      )
      (libsource (lib "Resistors") (part "Resistor - 1%"))
    )
    (comp (ref "R63")
      (value "2k7")
      (footprint "RESC1608X55N")
      (description "Resistor - 1%")
      (fields
        (field (name "PART NUMBER") "R0603_2K7_1%_0.1W_100PPM")
        (field (name "POWER") "0.1W")
        (field (name "AUTHOR") "CERN DEM JLC")
      )
      (libsource (lib "Resistors") (part "Resistor - 1%"))
    )
    (comp (ref "R64")
      (value "24k")
      (footprint "RESC1608X55N")
      (description "Resistor - 1%")
      (fields
        (field (name "PART NUMBER") "R0603_24K_1%_0.1W_100PPM")
        (field (name "POWER") "0.1W")
        (field (name "AUTHOR") "CERN DEM JLC")
      )
      (libsource (lib "Resistors") (part "Resistor - 1%"))
    )
    (comp (ref "R65")
      (value "5k1")
      (footprint "RESC1005X40N")
      (description "Resistor - 1%")
      (fields
        (field (name "PART NUMBER") "R0402_5K1_1%_0.0625W_100PPM")
        (field (name "POWER") "0.0625W")
        (field (name "AUTHOR") "CERN DEM JLC")
      )
      (libsource (lib "Resistors") (part "Resistor - 1%"))
    )
    (comp (ref "R66")
      (value "270k")
      (footprint "RESC1608X55N")
      (description "Resistor - 1%")
      (fields
        (field (name "PART NUMBER") "R0603_270K_1%_0.1W_100PPM")
        (field (name "POWER") "0.1W")
        (field (name "AUTHOR") "CERN DEM JLC")
      )
      (libsource (lib "Resistors") (part "Resistor - 1%"))
    )
    (comp (ref "R67")
      (value "24k")
      (footprint "RESC1608X55N")
      (description "Resistor - 1%")
      (fields
        (field (name "PART NUMBER") "R0603_24K_1%_0.1W_100PPM")
        (field (name "POWER") "0.1W")
        (field (name "AUTHOR") "CERN DEM JLC")
      )
      (libsource (lib "Resistors") (part "Resistor - 1%"))
    )
    (comp (ref "R68")
      (value "82k")
      (footprint "RESC1608X55N")
      (description "Resistor - 1%")
      (fields
        (field (name "PART NUMBER") "R0603_82K_1%_0.1W_100PPM")
        (field (name "POWER") "0.1W")
        (field (name "AUTHOR") "CERN DEM JLC")
      )
      (libsource (lib "Resistors") (part "Resistor - 1%"))
    )
    (comp (ref "R69")
      (value "5k1")
      (footprint "RESC1005X40N")
      (description "Resistor - 1%")
      (fields
        (field (name "PART NUMBER") "R0402_5K1_1%_0.0625W_100PPM")
        (field (name "POWER") "0.0625W")
        (field (name "AUTHOR") "CERN DEM JLC")
      )
      (libsource (lib "Resistors") (part "Resistor - 1%"))
    )
    (comp (ref "R70")
      (value "36k")
      (footprint "RESC1608X55N")
      (description "Resistor - 1%")
      (fields
        (field (name "PART NUMBER") "R0603_36K_1%_0.1W_100PPM")
        (field (name "POWER") "0.1W")
        (field (name "TOLERANCE") "±1%")
        (field (name "AUTHOR") "CERN DEM JLC")
      )
      (libsource (lib "") (part "Resistor - 1%_1"))
    )
    (comp (ref "R71")
      (value "33k")
      (footprint "RESC1005X40N")
      (description "Resistor - 1%")
      (fields
        (field (name "PART NUMBER") "R0402_33K_1%_0.0625W_100PPM")
        (field (name "POWER") "0.0625W")
        (field (name "AUTHOR") "CERN DEM JLC")
      )
      (libsource (lib "Resistors") (part "Resistor - 1%"))
    )
    (comp (ref "R72")
      (value "33k")
      (footprint "RESC1005X40N")
      (description "Resistor - 1%")
      (fields
        (field (name "PART NUMBER") "R0402_33K_1%_0.0625W_100PPM")
        (field (name "POWER") "0.0625W")
        (field (name "AUTHOR") "CERN DEM JLC")
      )
      (libsource (lib "Resistors") (part "Resistor - 1%"))
    )
    (comp (ref "R73")
      (value "62k")
      (footprint "RESC1005X40N")
      (description "Resistor - 1%")
      (fields
        (field (name "PART NUMBER") "R0402_62K_1%_0.0625W_100PPM")
        (field (name "POWER") "0.0625W")
        (field (name "AUTHOR") "CERN DEM JLC")
      )
      (libsource (lib "Resistors") (part "Resistor - 1%"))
    )
    (comp (ref "R74")
      (value "5k1")
      (footprint "RESC1005X40N")
      (description "Resistor - 1%")
      (fields
        (field (name "PART NUMBER") "R0402_5K1_1%_0.0625W_100PPM")
        (field (name "POWER") "0.0625W")
        (field (name "AUTHOR") "CERN DEM JLC")
      )
      (libsource (lib "Resistors") (part "Resistor - 1%"))
    )
    (comp (ref "R75")
      (value "10k")
      (footprint "RESC1005X40N")
      (description "Resistor - 1%")
      (fields
        (field (name "PART NUMBER") "R0402_10K_1%_0.0625W_100PPM")
        (field (name "POWER") "0.0625W")
        (field (name "AUTHOR") "CERN DEM JLC")
      )
      (libsource (lib "Resistors") (part "Resistor - 1%"))
    )
    (comp (ref "R80")
      (value "0")
      (footprint "RESC1005X40N")
      (description "Resistor")
      (fields
        (field (name "PART NUMBER") "R0402_0R_JUMPER")
        (field (name "MANUFACTURER") "GENERIC")
        (field (name "AUTHOR") "CERN DEM JLC")
      )
      (libsource (lib "Resistors") (part "Resistor"))
    )
    (comp (ref "R82")
      (value "0")
      (footprint "RESC1005X40N")
      (description "Resistor")
      (fields
        (field (name "PART NUMBER") "R0402_0R_JUMPER")
        (field (name "MANUFACTURER") "GENERIC")
        (field (name "AUTHOR") "CERN DEM JLC")
      )
      (libsource (lib "Resistors") (part "Resistor"))
    )
    (comp (ref "R157")
      (value "0")
      (footprint "RESC1005X40N")
      (description "Resistor")
      (fields
        (field (name "PART NUMBER") "R0402_0R_JUMPER")
        (field (name "MANUFACTURER") "GENERIC")
        (field (name "AUTHOR") "CERN DEM JLC")
      )
      (libsource (lib "Resistors") (part "Resistor"))
    )
  )
  (nets
    (net (code "1") (name "/PGOOD") (class "Default")
      (node (ref "R157") (pin "2") (pinfunction "2_2") (pintype "passive"))
    )
    (net (code "2") (name "/PSU_EN") (class "Default")
      (node (ref "IC31") (pin "3") (pinfunction "EN_3") (pintype "input"))
    )
    (net (code "3") (name "/REF_~{SHD}N") (class "Default")
      (node (ref "D10") (pin "1") (pinfunction "C_1") (pintype "passive"))
      (node (ref "IC28") (pin "7") (pinfunction "PG_7") (pintype "output"))
      (node (ref "IC33") (pin "1") (pinfunction "~{SHDN}_1") (pintype "input"))
      (node (ref "IC34") (pin "1") (pinfunction "~{SHDN}_1") (pintype "input"))
      (node (ref "R157") (pin "1") (pinfunction "1_1") (pintype "passive"))
      (node (ref "R69") (pin "1") (pinfunction "1_1") (pintype "passive"))
    )
    (net (code "4") (name "/SR_~{OE}") (class "Default")
      (node (ref "IC27") (pin "7") (pinfunction "OUT_7") (pintype "output"))
      (node (ref "R65") (pin "1") (pinfunction "1_1") (pintype "passive"))
    )
    (net (code "5") (name "GND") (class "Default")
      (node (ref "C100") (pin "1") (pinfunction "1_1") (pintype "passive"))
      (node (ref "C101") (pin "1") (pinfunction "1_1") (pintype "passive"))
      (node (ref "C102") (pin "1") (pinfunction "1_1") (pintype "passive"))
      (node (ref "C26") (pin "1") (pinfunction "1_1") (pintype "passive"))
      (node (ref "C29") (pin "1") (pinfunction "1_1") (pintype "passive"))
      (node (ref "C37") (pin "1") (pinfunction "1_1") (pintype "passive"))
      (node (ref "C38") (pin "2") (pinfunction "2_2") (pintype "passive"))
      (node (ref "C39") (pin "1") (pinfunction "1_1") (pintype "passive"))
      (node (ref "C41") (pin "1") (pinfunction "1_1") (pintype "passive"))
      (node (ref "C43") (pin "1") (pinfunction "1_1") (pintype "passive"))
      (node (ref "C44") (pin "2") (pinfunction "2_2") (pintype "passive"))
      (node (ref "C45") (pin "1") (pinfunction "1_1") (pintype "passive"))
      (node (ref "C47") (pin "2") (pinfunction "2_2") (pintype "passive"))
      (node (ref "C48") (pin "1") (pinfunction "1_1") (pintype "passive"))
      (node (ref "C49") (pin "1") (pinfunction "1_1") (pintype "passive"))
      (node (ref "C50") (pin "2") (pinfunction "2_2") (pintype "passive"))
      (node (ref "C51") (pin "1") (pinfunction "1_1") (pintype "passive"))
      (node (ref "C52") (pin "2") (pinfunction "2_2") (pintype "passive"))
      (node (ref "C53") (pin "1") (pinfunction "1_1") (pintype "passive"))
      (node (ref "C54") (pin "1") (pinfunction "1_1") (pintype "passive"))
      (node (ref "C55") (pin "1") (pinfunction "1_1") (pintype "passive"))
      (node (ref "C56") (pin "1") (pinfunction "1_1") (pintype "passive"))
      (node (ref "C57") (pin "1") (pinfunction "1_1") (pintype "passive"))
      (node (ref "C58") (pin "1") (pinfunction "1_1") (pintype "passive"))
      (node (ref "C59") (pin "1") (pinfunction "1_1") (pintype "passive"))
      (node (ref "C60") (pin "1") (pinfunction "1_1") (pintype "passive"))
      (node (ref "C61") (pin "1") (pinfunction "1_1") (pintype "passive"))
      (node (ref "C62") (pin "1") (pinfunction "1_1") (pintype "passive"))
      (node (ref "C63") (pin "1") (pinfunction "1_1") (pintype "passive"))
      (node (ref "C64") (pin "1") (pinfunction "1_1") (pintype "passive"))
      (node (ref "C65") (pin "1") (pinfunction "1_1") (pintype "passive"))
      (node (ref "C66") (pin "1") (pinfunction "1_1") (pintype "passive"))
      (node (ref "C67") (pin "2") (pinfunction "2_2") (pintype "passive"))
      (node (ref "C68") (pin "1") (pinfunction "1_1") (pintype "passive"))
      (node (ref "C69") (pin "1") (pinfunction "1_1") (pintype "passive"))
      (node (ref "C70") (pin "1") (pinfunction "1_1") (pintype "passive"))
      (node (ref "C71") (pin "1") (pinfunction "1_1") (pintype "passive"))
      (node (ref "C72") (pin "1") (pinfunction "1_1") (pintype "passive"))
      (node (ref "C73") (pin "1") (pinfunction "1_1") (pintype "passive"))
      (node (ref "C74") (pin "1") (pinfunction "1_1") (pintype "passive"))
      (node (ref "C76") (pin "1") (pinfunction "1_1") (pintype "passive"))
      (node (ref "C77") (pin "2") (pinfunction "2_2") (pintype "passive"))
      (node (ref "C78") (pin "1") (pinfunction "1_1") (pintype "passive"))
      (node (ref "C79") (pin "1") (pinfunction "1_1") (pintype "passive"))
      (node (ref "C80") (pin "2") (pinfunction "2_2") (pintype "passive"))
      (node (ref "C81") (pin "1") (pinfunction "1_1") (pintype "passive"))
      (node (ref "C83") (pin "1") (pinfunction "1_1") (pintype "passive"))
      (node (ref "C84") (pin "2") (pinfunction "2_2") (pintype "passive"))
      (node (ref "C85") (pin "1") (pinfunction "1_1") (pintype "passive"))
      (node (ref "C86") (pin "1") (pinfunction "1_1") (pintype "passive"))
      (node (ref "D5") (pin "2") (pinfunction "A_2") (pintype "passive"))
      (node (ref "D6") (pin "1") (pinfunction "C_1") (pintype "passive"))
      (node (ref "IC21") (pin "3") (pinfunction "GND_3") (pintype "power_in"))
      (node (ref "IC21") (pin "6") (pinfunction "GND_6") (pintype "power_in"))
      (node (ref "IC21") (pin "7") (pinfunction "GND_7") (pintype "power_in"))
      (node (ref "IC22") (pin "2") (pinfunction "GND_2") (pintype "power_in"))
      (node (ref "IC23") (pin "2") (pinfunction "GND_2") (pintype "power_in"))
      (node (ref "IC24") (pin "6") (pinfunction "GND_6") (pintype "power_in"))
      (node (ref "IC25") (pin "3") (pinfunction "-Vin_3") (pintype "power_in"))
      (node (ref "IC25") (pin "5") (pinfunction "COM_5") (pintype "power_in"))
      (node (ref "IC25") (pin "8") (pinfunction "Shield_8") (pintype "power_in"))
      (node (ref "IC26") (pin "1") (pinfunction "GND_1") (pintype "power_in"))
      (node (ref "IC27") (pin "4") (pinfunction "V-_4") (pintype "power_in"))
      (node (ref "IC28") (pin "1") (pinfunction "PGND_1") (pintype "power_in"))
      (node (ref "IC28") (pin "11") (pinfunction "EP_11") (pintype "power_in"))
      (node (ref "IC28") (pin "6") (pinfunction "AGND_6") (pintype "power_in"))
      (node (ref "IC29") (pin "2") (pinfunction "GND_2") (pintype "power_in"))
      (node (ref "IC30") (pin "2") (pinfunction "GND_2") (pintype "power_in"))
      (node (ref "IC31") (pin "1") (pinfunction "PGND_1") (pintype "power_in"))
      (node (ref "IC31") (pin "11") (pinfunction "EP_11") (pintype "power_in"))
      (node (ref "IC31") (pin "6") (pinfunction "AGND_6") (pintype "power_in"))
      (node (ref "IC32") (pin "3") (pinfunction "GND_3") (pintype "power_in"))
      (node (ref "IC32") (pin "6") (pinfunction "GND_6") (pintype "power_in"))
      (node (ref "IC32") (pin "7") (pinfunction "GND_7") (pintype "power_in"))
      (node (ref "IC33") (pin "3") (pinfunction "GND_3") (pintype "power_in"))
      (node (ref "IC33") (pin "4") (pinfunction "GND_4") (pintype "power_in"))
      (node (ref "IC33") (pin "5") (pinfunction "GND_5") (pintype "power_in"))
      (node (ref "IC33") (pin "8") (pinfunction "GND_8") (pintype "power_in"))
      (node (ref "IC34") (pin "3") (pinfunction "GND_3") (pintype "power_in"))
      (node (ref "IC34") (pin "4") (pinfunction "GND_4") (pintype "power_in"))
      (node (ref "IC34") (pin "5") (pinfunction "GND_5") (pintype "power_in"))
      (node (ref "IC34") (pin "8") (pinfunction "GND_8") (pintype "power_in"))
      (node (ref "R35") (pin "1") (pinfunction "1_1") (pintype "passive"))
      (node (ref "R52") (pin "1") (pinfunction "1_1") (pintype "passive"))
      (node (ref "R55") (pin "1") (pinfunction "1_1") (pintype "passive"))
      (node (ref "R57") (pin "1") (pinfunction "1_1") (pintype "passive"))
      (node (ref "R62") (pin "1") (pinfunction "1_1") (pintype "passive"))
      (node (ref "R63") (pin "1") (pinfunction "1_1") (pintype "passive"))
      (node (ref "R68") (pin "1") (pinfunction "1_1") (pintype "passive"))
      (node (ref "R71") (pin "1") (pinfunction "1_1") (pintype "passive"))
      (node (ref "R74") (pin "1") (pinfunction "1_1") (pintype "passive"))
    )
    (net (code "6") (name "N12V0A") (class "Default")
      (node (ref "C46") (pin "2") (pinfunction "2_2") (pintype "passive"))
      (node (ref "C63") (pin "2") (pinfunction "2_2") (pintype "passive"))
      (node (ref "C64") (pin "2") (pinfunction "2_2") (pintype "passive"))
      (node (ref "D6") (pin "2") (pinfunction "A_2") (pintype "passive"))
      (node (ref "IC24") (pin "1") (pinfunction "OUT_1") (pintype "power_in"))
      (node (ref "IC24") (pin "2") (pinfunction "OUT_2") (pintype "power_in"))
      (node (ref "IC26") (pin "5") (pinfunction "OUT_5") (pintype "power_in"))
      (node (ref "R61") (pin "2") (pinfunction "2_2") (pintype "passive"))
    )
    (net (code "7") (name "N13V0") (class "Default")
      (node (ref "C26") (pin "2") (pinfunction "2_2") (pintype "passive"))
      (node (ref "C61") (pin "2") (pinfunction "2_2") (pintype "passive"))
      (node (ref "C62") (pin "2") (pinfunction "2_2") (pintype "passive"))
      (node (ref "IC24") (pin "7") (pinfunction "IN_7") (pintype "power_in"))
      (node (ref "IC24") (pin "8") (pinfunction "IN_8") (pintype "power_in"))
      (node (ref "IC24") (pin "9") (pinfunction "IN_9") (pintype "power_in"))
      (node (ref "IC26") (pin "2") (pinfunction "IN_2") (pintype "input"))
      (node (ref "L6") (pin "2") (pinfunction "2_2") (pintype "passive"))
    )
    (net (code "8") (name "N13V0S") (class "Default")
      (node (ref "C58") (pin "2") (pinfunction "2_2") (pintype "passive"))
      (node (ref "IC25") (pin "4") (pinfunction "-Vout_4") (pintype "power_in"))
      (node (ref "L5") (pin "1") (pinfunction "1_1") (pintype "passive"))
      (node (ref "R58") (pin "1") (pinfunction "1_1") (pintype "passive"))
    )
    (net (code "9") (name "Net-(C49-Pad2)") (class "Default")
      (node (ref "C49") (pin "2") (pinfunction "2_2") (pintype "passive"))
      (node (ref "C50") (pin "1") (pinfunction "1_1") (pintype "passive"))
      (node (ref "L2") (pin "2") (pinfunction "2_2") (pintype "passive"))
      (node (ref "L3") (pin "1") (pinfunction "1_1") (pintype "passive"))
    )
    (net (code "10") (name "Net-(C59-Pad2)") (class "Default")
      (node (ref "C59") (pin "2") (pinfunction "2_2") (pintype "passive"))
      (node (ref "C60") (pin "2") (pinfunction "2_2") (pintype "passive"))
      (node (ref "L5") (pin "2") (pinfunction "2_2") (pintype "passive"))
      (node (ref "L6") (pin "1") (pinfunction "1_1") (pintype "passive"))
    )
    (net (code "11") (name "Net-(D7-A)") (class "Default")
      (node (ref "C65") (pin "2") (pinfunction "2_2") (pintype "passive"))
      (node (ref "D7") (pin "2") (pinfunction "A_2") (pintype "passive"))
      (node (ref "IC27") (pin "3") (pinfunction "IN+_3") (pintype "input"))
      (node (ref "R59") (pin "1") (pinfunction "1_1") (pintype "passive"))
      (node (ref "R62") (pin "2") (pinfunction "2_2") (pintype "passive"))
    )
    (net (code "12") (name "Net-(D8-A)") (class "Default")
      (node (ref "C66") (pin "2") (pinfunction "2_2") (pintype "passive"))
      (node (ref "D8") (pin "2") (pinfunction "A_2") (pintype "passive"))
      (node (ref "IC28") (pin "3") (pinfunction "EN_3") (pintype "input"))
      (node (ref "IC31") (pin "7") (pinfunction "PG_7") (pintype "output"))
      (node (ref "R64") (pin "1") (pinfunction "1_1") (pintype "passive"))
    )
    (net (code "13") (name "Net-(D9-A)") (class "Default")
      (node (ref "C72") (pin "2") (pinfunction "2_2") (pintype "passive"))
      (node (ref "D9") (pin "2") (pinfunction "A_2") (pintype "passive"))
      (node (ref "IC27") (pin "6") (pinfunction "IN-_6") (pintype "input"))
      (node (ref "R67") (pin "1") (pinfunction "1_1") (pintype "passive"))
    )
    (net (code "14") (name "Net-(D10-A)") (class "Default")
      (node (ref "D10") (pin "2") (pinfunction "A_2") (pintype "passive"))
      (node (ref "IC21") (pin "5") (pinfunction "~{SHDN}_5") (pintype "input"))
      (node (ref "IC24") (pin "4") (pinfunction "~{SHDN}_4") (pintype "input"))
      (node (ref "IC26") (pin "3") (pinfunction "~{SHDN}_3") (pintype "input"))
      (node (ref "IC27") (pin "1") (pinfunction "OUT_1") (pintype "output"))
      (node (ref "R53") (pin "1") (pinfunction "1_1") (pintype "passive"))
      (node (ref "R67") (pin "2") (pinfunction "2_2") (pintype "passive"))
    )
    (net (code "15") (name "Net-(IC21-ADJ)") (class "Default")
      (node (ref "IC21") (pin "2") (pinfunction "ADJ_2") (pintype "input"))
      (node (ref "R51") (pin "1") (pinfunction "1_1") (pintype "passive"))
      (node (ref "R52") (pin "2") (pinfunction "2_2") (pintype "passive"))
    )
    (net (code "16") (name "Net-(IC21-BYP)") (class "Default")
      (node (ref "C40") (pin "2") (pinfunction "2_2") (pintype "passive"))
      (node (ref "IC21") (pin "4") (pinfunction "BYP_4") (pintype "passive"))
    )
    (net (code "17") (name "Net-(IC22-ADJ)") (class "Default")
      (node (ref "IC22") (pin "4") (pinfunction "ADJ_4") (pintype "input"))
      (node (ref "IC23") (pin "4") (pinfunction "ADJ_4") (pintype "input"))
      (node (ref "R54") (pin "1") (pinfunction "1_1") (pintype "passive"))
      (node (ref "R55") (pin "2") (pinfunction "2_2") (pintype "passive"))
    )
    (net (code "18") (name "Net-(IC23-BYP)") (class "Default")
      (node (ref "C42") (pin "1") (pinfunction "1_1") (pintype "passive"))
      (node (ref "IC23") (pin "3") (pinfunction "BYP_3") (pintype "input"))
    )
    (net (code "19") (name "Net-(IC24-ADJ)") (class "Default")
      (node (ref "IC24") (pin "3") (pinfunction "ADJ_3") (pintype "input"))
      (node (ref "IC26") (pin "4") (pinfunction "ADJ_4") (pintype "input"))
      (node (ref "R61") (pin "1") (pinfunction "1_1") (pintype "passive"))
      (node (ref "R63") (pin "2") (pinfunction "2_2") (pintype "passive"))
    )
    (net (code "20") (name "Net-(IC24-BYP)") (class "Default")
      (node (ref "C46") (pin "1") (pinfunction "1_1") (pintype "passive"))
      (node (ref "IC24") (pin "5") (pinfunction "BYP_5") (pintype "passive"))
    )
    (net (code "21") (name "Net-(IC25-+Vin)") (class "Default")
      (node (ref "C52") (pin "1") (pinfunction "1_1") (pintype "passive"))
      (node (ref "C53") (pin "2") (pinfunction "2_2") (pintype "passive"))
      (node (ref "C54") (pin "2") (pinfunction "2_2") (pintype "passive"))
      (node (ref "C55") (pin "2") (pinfunction "2_2") (pintype "passive"))
      (node (ref "C56") (pin "2") (pinfunction "2_2") (pintype "passive"))
      (node (ref "C73") (pin "2") (pinfunction "2_2") (pintype "passive"))
      (node (ref "C74") (pin "2") (pinfunction "2_2") (pintype "passive"))
      (node (ref "C85") (pin "2") (pinfunction "2_2") (pintype "passive"))
      (node (ref "C86") (pin "2") (pinfunction "2_2") (pintype "passive"))
      (node (ref "IC25") (pin "1") (pinfunction "+Vin_1") (pintype "power_in"))
      (node (ref "IC28") (pin "2") (pinfunction "VIN_2") (pintype "input"))
      (node (ref "IC31") (pin "2") (pinfunction "VIN_2") (pintype "input"))
      (node (ref "L4") (pin "2") (pinfunction "2_2") (pintype "passive"))
    )
    (net (code "22") (name "Net-(IC25-RC)") (class "Default")
      (node (ref "IC25") (pin "2") (pinfunction "RC_2") (pintype "input"))
      (node (ref "R57") (pin "2") (pinfunction "2_2") (pintype "passive"))
    )
    (net (code "23") (name "Net-(IC25-TRM)") (class "Default")
      (node (ref "IC25") (pin "6") (pinfunction "TRM_6") (pintype "power_in"))
      (node (ref "R56") (pin "1") (pinfunction "1_1") (pintype "passive"))
      (node (ref "R58") (pin "2") (pinfunction "2_2") (pintype "passive"))
    )
    (net (code "24") (name "Net-(IC27A-IN-)") (class "Default")
      (node (ref "IC27") (pin "2") (pinfunction "IN-_2") (pintype "input"))
      (node (ref "R60") (pin "1") (pinfunction "1_1") (pintype "passive"))
    )
    (net (code "25") (name "Net-(IC28-FB)") (class "Default")
      (node (ref "IC28") (pin "5") (pinfunction "FB_5") (pintype "input"))
      (node (ref "R66") (pin "1") (pinfunction "1_1") (pintype "passive"))
      (node (ref "R68") (pin "2") (pinfunction "2_2") (pintype "passive"))
    )
    (net (code "26") (name "Net-(IC28-SW)") (class "Default")
      (node (ref "IC28") (pin "9") (pinfunction "SW_9") (pintype "output"))
      (node (ref "L7") (pin "1") (pinfunction "1_1") (pintype "passive"))
    )
    (net (code "27") (name "Net-(IC29-ADJ)") (class "Default")
      (node (ref "IC29") (pin "4") (pinfunction "ADJ_4") (pintype "input"))
      (node (ref "IC30") (pin "4") (pinfunction "ADJ_4") (pintype "input"))
      (node (ref "R70") (pin "1") (pinfunction "1_1") (pintype "passive"))
      (node (ref "R71") (pin "2") (pinfunction "2_2") (pintype "passive"))
    )
    (net (code "28") (name "Net-(IC30-BYP)") (class "Default")
      (node (ref "C75") (pin "1") (pinfunction "1_1") (pintype "passive"))
      (node (ref "IC30") (pin "3") (pinfunction "BYP_3") (pintype "input"))
    )
    (net (code "29") (name "Net-(IC31-FB)") (class "Default")
      (node (ref "IC31") (pin "5") (pinfunction "FB_5") (pintype "input"))
      (node (ref "R72") (pin "1") (pinfunction "1_1") (pintype "passive"))
      (node (ref "R74") (pin "2") (pinfunction "2_2") (pintype "passive"))
    )
    (net (code "30") (name "Net-(IC31-SW)") (class "Default")
      (node (ref "IC31") (pin "9") (pinfunction "SW_9") (pintype "output"))
      (node (ref "L9") (pin "1") (pinfunction "1_1") (pintype "passive"))
    )
    (net (code "31") (name "Net-(IC32-ADJ)") (class "Default")
      (node (ref "IC32") (pin "2") (pinfunction "ADJ_2") (pintype "input"))
      (node (ref "R73") (pin "1") (pinfunction "1_1") (pintype "passive"))
      (node (ref "R75") (pin "2") (pinfunction "2_2") (pintype "passive"))
    )
    (net (code "32") (name "Net-(IC32-BYP)") (class "Default")
      (node (ref "C82") (pin "2") (pinfunction "2_2") (pintype "passive"))
      (node (ref "IC32") (pin "4") (pinfunction "BYP_4") (pintype "passive"))
    )
    (net (code "33") (name "Net-(IC33-VIN)") (class "Default")
      (node (ref "C101") (pin "2") (pinfunction "2_2") (pintype "passive"))
      (node (ref "IC33") (pin "2") (pinfunction "VIN_2") (pintype "input"))
      (node (ref "IC34") (pin "2") (pinfunction "VIN_2") (pintype "input"))
      (node (ref "R80") (pin "2") (pinfunction "2_2") (pintype "passive"))
    )
    (net (code "34") (name "Net-(IC33-VOUTS{slash}NR)") (class "Default")
      (node (ref "C102") (pin "2") (pinfunction "2_2") (pintype "passive"))
      (node (ref "IC33") (pin "6") (pinfunction "VOUTS/NR_6") (pintype "power_in"))
      (node (ref "IC34") (pin "6") (pinfunction "VOUTS_6") (pintype "power_in"))
      (node (ref "R82") (pin "1") (pinfunction "1_1") (pintype "passive"))
    )
    (net (code "35") (name "Net-(R35-Pad2)") (class "Default")
      (node (ref "R35") (pin "2") (pinfunction "2_2") (pintype "passive"))
      (node (ref "R75") (pin "1") (pinfunction "1_1") (pintype "passive"))
    )
    (net (code "36") (name "P2V5A") (class "Default")
      (node (ref "C71") (pin "2") (pinfunction "2_2") (pintype "passive"))
      (node (ref "C75") (pin "2") (pinfunction "2_2") (pintype "passive"))
      (node (ref "C76") (pin "2") (pinfunction "2_2") (pintype "passive"))
      (node (ref "C77") (pin "1") (pinfunction "1_1") (pintype "passive"))
      (node (ref "IC29") (pin "5") (pinfunction "OUT_5") (pintype "power_in"))
      (node (ref "IC30") (pin "5") (pinfunction "OUT_5") (pintype "power_in"))
      (node (ref "R70") (pin "2") (pinfunction "2_2") (pintype "passive"))
    )
    (net (code "37") (name "P3V3") (class "Default")
      (node (ref "C69") (pin "2") (pinfunction "2_2") (pintype "passive"))
      (node (ref "C70") (pin "2") (pinfunction "2_2") (pintype "passive"))
      (node (ref "D9") (pin "1") (pinfunction "C_1") (pintype "passive"))
      (node (ref "IC27") (pin "5") (pinfunction "IN+_5") (pintype "input"))
      (node (ref "IC28") (pin "10") (pinfunction "VOS_10") (pintype "input"))
      (node (ref "IC28") (pin "8") (pinfunction "SLEEP_8") (pintype "input"))
      (node (ref "L7") (pin "2") (pinfunction "2_2") (pintype "passive"))
      (node (ref "L8") (pin "1") (pinfunction "1_1") (pintype "passive"))
      (node (ref "R65") (pin "2") (pinfunction "2_2") (pintype "passive"))
      (node (ref "R66") (pin "2") (pinfunction "2_2") (pintype "passive"))
    )
    (net (code "38") (name "P3V3A") (class "Default")
      (node (ref "C67") (pin "1") (pinfunction "1_1") (pintype "passive"))
      (node (ref "C68") (pin "2") (pinfunction "2_2") (pintype "passive"))
      (node (ref "D7") (pin "1") (pinfunction "C_1") (pintype "passive"))
      (node (ref "IC29") (pin "1") (pinfunction "IN_1") (pintype "input"))
      (node (ref "IC29") (pin "3") (pinfunction "~{SHDN}_3") (pintype "input"))
      (node (ref "IC30") (pin "1") (pinfunction "IN_1") (pintype "input"))
      (node (ref "L8") (pin "2") (pinfunction "2_2") (pintype "passive"))
      (node (ref "R60") (pin "2") (pinfunction "2_2") (pintype "passive"))
    )
    (net (code "39") (name "P5V0A") (class "Default")
      (node (ref "C82") (pin "1") (pinfunction "1_1") (pintype "passive"))
      (node (ref "C83") (pin "2") (pinfunction "2_2") (pintype "passive"))
      (node (ref "C84") (pin "1") (pinfunction "1_1") (pintype "passive"))
      (node (ref "IC32") (pin "1") (pinfunction "OUT_1") (pintype "power_in"))
      (node (ref "R73") (pin "2") (pinfunction "2_2") (pintype "passive"))
    )
    (net (code "40") (name "P6V0") (class "Default")
      (node (ref "C78") (pin "2") (pinfunction "2_2") (pintype "passive"))
      (node (ref "C79") (pin "2") (pinfunction "2_2") (pintype "passive"))
      (node (ref "IC31") (pin "10") (pinfunction "VOS_10") (pintype "input"))
      (node (ref "IC31") (pin "8") (pinfunction "SLEEP_8") (pintype "input"))
      (node (ref "L10") (pin "1") (pinfunction "1_1") (pintype "passive"))
      (node (ref "L9") (pin "2") (pinfunction "2_2") (pintype "passive"))
      (node (ref "R69") (pin "2") (pinfunction "2_2") (pintype "passive"))
      (node (ref "R72") (pin "2") (pinfunction "2_2") (pintype "passive"))
    )
    (net (code "41") (name "P6V0A") (class "Default")
      (node (ref "C80") (pin "1") (pinfunction "1_1") (pintype "passive"))
      (node (ref "C81") (pin "2") (pinfunction "2_2") (pintype "passive"))
      (node (ref "D8") (pin "1") (pinfunction "C_1") (pintype "passive"))
      (node (ref "IC32") (pin "5") (pinfunction "~{SHDN}_5") (pintype "input"))
      (node (ref "IC32") (pin "8") (pinfunction "IN_8") (pintype "input"))
      (node (ref "L10") (pin "2") (pinfunction "2_2") (pintype "passive"))
      (node (ref "R53") (pin "2") (pinfunction "2_2") (pintype "passive"))
      (node (ref "R64") (pin "2") (pinfunction "2_2") (pintype "passive"))
    )
    (net (code "42") (name "P12V0") (class "Default")
      (node (ref "C29") (pin "2") (pinfunction "2_2") (pintype "passive"))
      (node (ref "C57") (pin "2") (pinfunction "2_2") (pintype "passive"))
      (node (ref "IC27") (pin "8") (pinfunction "V+_8") (pintype "power_in"))
      (node (ref "L4") (pin "1") (pinfunction "1_1") (pintype "passive"))
    )
    (net (code "43") (name "P12V0A") (class "Default")
      (node (ref "C38") (pin "1") (pinfunction "1_1") (pintype "passive"))
      (node (ref "C39") (pin "2") (pinfunction "2_2") (pintype "passive"))
      (node (ref "C40") (pin "1") (pinfunction "1_1") (pintype "passive"))
      (node (ref "D5") (pin "1") (pinfunction "C_1") (pintype "passive"))
      (node (ref "IC21") (pin "1") (pinfunction "OUT_1") (pintype "power_in"))
      (node (ref "R51") (pin "2") (pinfunction "2_2") (pintype "passive"))
    )
    (net (code "44") (name "P13V0") (class "Default")
      (node (ref "C37") (pin "2") (pinfunction "2_2") (pintype "passive"))
      (node (ref "C43") (pin "2") (pinfunction "2_2") (pintype "passive"))
      (node (ref "C47") (pin "1") (pinfunction "1_1") (pintype "passive"))
      (node (ref "C51") (pin "2") (pinfunction "2_2") (pintype "passive"))
      (node (ref "IC21") (pin "8") (pinfunction "IN_8") (pintype "input"))
      (node (ref "IC22") (pin "1") (pinfunction "IN_1") (pintype "input"))
      (node (ref "IC22") (pin "3") (pinfunction "~{SHDN}_3") (pintype "input"))
      (node (ref "IC23") (pin "1") (pinfunction "IN_1") (pintype "input"))
      (node (ref "L3") (pin "2") (pinfunction "2_2") (pintype "passive"))
    )
    (net (code "45") (name "P13V0S") (class "Default")
      (node (ref "C48") (pin "2") (pinfunction "2_2") (pintype "passive"))
      (node (ref "IC25") (pin "7") (pinfunction "+Vout_7") (pintype "power_in"))
      (node (ref "L2") (pin "1") (pinfunction "1_1") (pintype "passive"))
      (node (ref "R56") (pin "2") (pinfunction "2_2") (pintype "passive"))
    )
    (net (code "46") (name "REF_P4V096") (class "Default")
      (node (ref "C100") (pin "2") (pinfunction "2_2") (pintype "passive"))
      (node (ref "IC33") (pin "7") (pinfunction "VOUTF_7") (pintype "power_in"))
      (node (ref "IC34") (pin "7") (pinfunction "VOUTF_7") (pintype "power_in"))
      (node (ref "R59") (pin "2") (pinfunction "2_2") (pintype "passive"))
      (node (ref "R82") (pin "2") (pinfunction "2_2") (pintype "passive"))
    )
    (net (code "47") (name "REF_VCC") (class "Default")
      (node (ref "C41") (pin "2") (pinfunction "2_2") (pintype "passive"))
      (node (ref "C42") (pin "2") (pinfunction "2_2") (pintype "passive"))
      (node (ref "C44") (pin "1") (pinfunction "1_1") (pintype "passive"))
      (node (ref "C45") (pin "2") (pinfunction "2_2") (pintype "passive"))
      (node (ref "IC22") (pin "5") (pinfunction "OUT_5") (pintype "power_in"))
      (node (ref "IC23") (pin "5") (pinfunction "OUT_5") (pintype "power_in"))
      (node (ref "R54") (pin "2") (pinfunction "2_2") (pintype "passive"))
      (node (ref "R80") (pin "1") (pinfunction "1_1") (pintype "passive"))
    )
    (net (code "48") (name "unconnected-(IC28-NC-Pad4)") (class "Default")
      (node (ref "IC28") (pin "4") (pinfunction "NC_4") (pintype "passive"))
    )
    (net (code "49") (name "unconnected-(IC31-NC-Pad4)") (class "Default")
      (node (ref "IC31") (pin "4") (pinfunction "NC_4") (pintype "passive"))
    )
  )
)
